# SCH_ESP32-Gate-Module_2024-04-19.net
KiCad netlist of a schematic drawn in EasyEDA
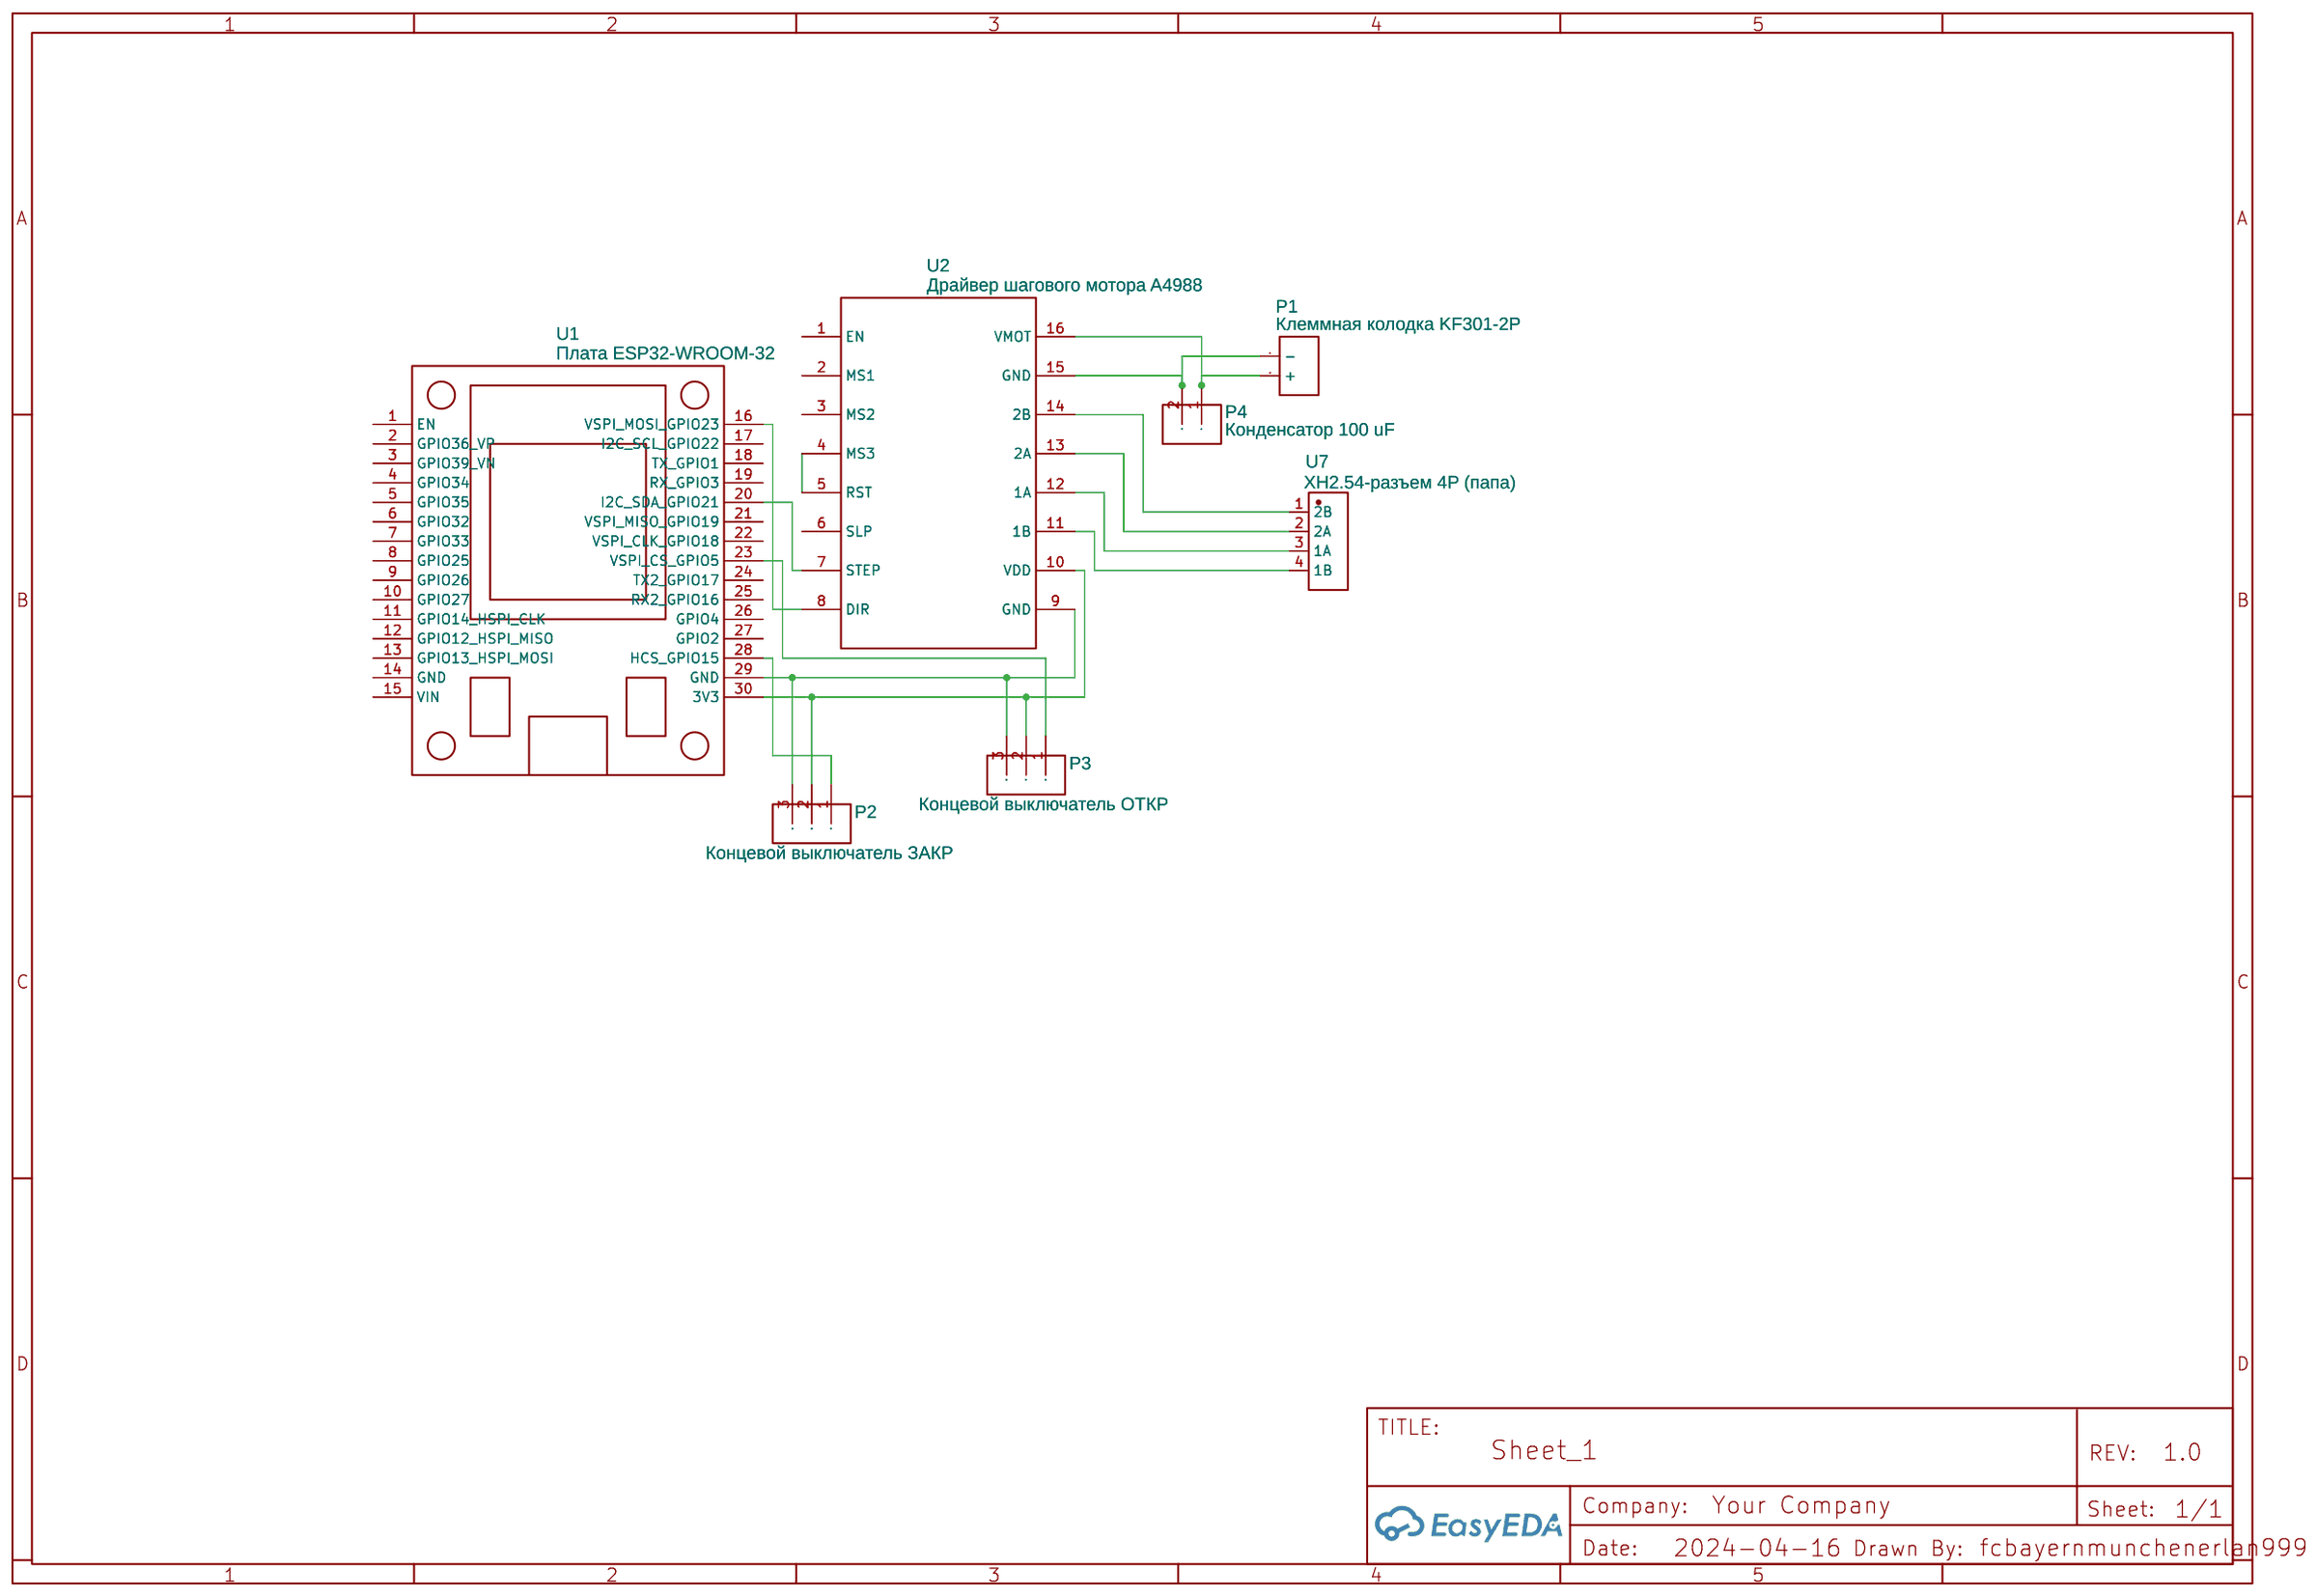
[diagram p0: schematic sheet]

(export (version "E")
  (design (tool "Eeschema 10.0.6"))
  (components
    (comp (ref "P1") (value "Клеммная колодка KF301-2P") (libsource (lib "") (part "CONN-TH_2P-P5.00")))
    (comp (ref "P2") (value "Концевой выключатель ЗАКР") (libsource (lib "") (part "3x2.54 XHP-3 JST case")))
    (comp (ref "P3") (value "Концевой выключатель ОТКР") (libsource (lib "") (part "3x2.54 XHP-3 JST case")))
    (comp (ref "P4") (value "Конденсатор 100 uF") (libsource (lib "") (part "2x2.54 XHP-2 JST case")))
    (comp (ref "U1") (value "Плата ESP32-WROOM-32") (libsource (lib "") (part "Плата ESP32 (вариант 2)")))
    (comp (ref "U2")
      (value "Драйвер шагового мотора A4988")
      (libsource (lib "") (part "A4988 Stepper Motor Driver Carrier"))
    )
    (comp (ref "U7")
      (value "XH2.54-разъем 4P (папа)")
      (fields
        (field (name "Manufacturer Part") "ZX-XH2.54-4PWZ")
        (field (name "Manufacturer") "Megastar(兆星)")
      )
      (libsource (lib "") (part "ZX-XH2.54-4PWZ"))
    )
  )
  (nets
    (net (code "1") (name "Net-(P1-+)") (class "Default")
      (node (ref "P1") (pin "2") (pinfunction "+_2") (pintype "unspecified"))
      (node (ref "P4") (pin "1") (pinfunction "1_1") (pintype "unspecified"))
      (node (ref "U2") (pin "16") (pinfunction "VMOT_16") (pintype "unspecified"))
    )
    (net (code "2") (name "Net-(P1--)") (class "Default")
      (node (ref "P1") (pin "1") (pinfunction "-_1") (pintype "unspecified"))
      (node (ref "P4") (pin "2") (pinfunction "2_2") (pintype "unspecified"))
      (node (ref "U2") (pin "15") (pinfunction "GND_15") (pintype "unspecified"))
    )
    (net (code "3") (name "Net-(P2-Pad3)") (class "Default")
      (node (ref "P2") (pin "3") (pinfunction "3_3") (pintype "unspecified"))
      (node (ref "P3") (pin "3") (pinfunction "3_3") (pintype "unspecified"))
      (node (ref "U1") (pin "29") (pinfunction "GND_29") (pintype "bidirectional"))
      (node (ref "U2") (pin "9") (pinfunction "GND_9") (pintype "unspecified"))
    )
    (net (code "4") (name "Net-(U1-3V3)") (class "Default")
      (node (ref "P2") (pin "2") (pinfunction "2_2") (pintype "unspecified"))
      (node (ref "P3") (pin "2") (pinfunction "2_2") (pintype "unspecified"))
      (node (ref "U1") (pin "30") (pinfunction "3V3_30") (pintype "bidirectional"))
      (node (ref "U2") (pin "10") (pinfunction "VDD_10") (pintype "unspecified"))
    )
    (net (code "5") (name "Net-(U1-HCS_GPIO15)") (class "Default")
      (node (ref "P2") (pin "1") (pinfunction "1_1") (pintype "unspecified"))
      (node (ref "U1") (pin "28") (pinfunction "HCS_GPIO15_28") (pintype "bidirectional"))
    )
    (net (code "6") (name "Net-(U1-I2C_SDA_GPIO21)") (class "Default")
      (node (ref "U1") (pin "20") (pinfunction "I2C_SDA_GPIO21_20") (pintype "bidirectional"))
      (node (ref "U2") (pin "7") (pinfunction "STEP_7") (pintype "unspecified"))
    )
    (net (code "7") (name "Net-(U1-VSPI_CS_GPIO5)") (class "Default")
      (node (ref "P3") (pin "1") (pinfunction "1_1") (pintype "unspecified"))
      (node (ref "U1") (pin "23") (pinfunction "VSPI_CS_GPIO5_23") (pintype "bidirectional"))
    )
    (net (code "8") (name "Net-(U1-VSPI_MOSI_GPIO23)") (class "Default")
      (node (ref "U1") (pin "16") (pinfunction "VSPI_MOSI_GPIO23_16") (pintype "passive"))
      (node (ref "U2") (pin "8") (pinfunction "DIR_8") (pintype "unspecified"))
    )
    (net (code "9") (name "Net-(U2-1A)") (class "Default")
      (node (ref "U2") (pin "12") (pinfunction "1A_12") (pintype "unspecified"))
      (node (ref "U7") (pin "3") (pinfunction "1A_3") (pintype "unspecified"))
    )
    (net (code "10") (name "Net-(U2-1B)") (class "Default")
      (node (ref "U2") (pin "11") (pinfunction "1B_11") (pintype "unspecified"))
      (node (ref "U7") (pin "4") (pinfunction "1B_4") (pintype "unspecified"))
    )
    (net (code "11") (name "Net-(U2-2A)") (class "Default")
      (node (ref "U2") (pin "13") (pinfunction "2A_13") (pintype "unspecified"))
      (node (ref "U7") (pin "2") (pinfunction "2A_2") (pintype "unspecified"))
    )
    (net (code "12") (name "Net-(U2-2B)") (class "Default")
      (node (ref "U2") (pin "14") (pinfunction "2B_14") (pintype "unspecified"))
      (node (ref "U7") (pin "1") (pinfunction "2B_1") (pintype "unspecified"))
    )
    (net (code "13") (name "Net-(U2-MS3)") (class "Default")
      (node (ref "U2") (pin "4") (pinfunction "MS3_4") (pintype "unspecified"))
      (node (ref "U2") (pin "5") (pinfunction "RST_5") (pintype "unspecified"))
    )
    (net (code "14") (name "unconnected-(U1-EN-Pad1)") (class "Default")
      (node (ref "U1") (pin "1") (pinfunction "EN_1") (pintype "passive"))
    )
    (net (code "15") (name "unconnected-(U1-GND-Pad14)") (class "Default")
      (node (ref "U1") (pin "14") (pinfunction "GND_14") (pintype "passive"))
    )
    (net (code "16") (name "unconnected-(U1-GPIO2-Pad27)") (class "Default")
      (node (ref "U1") (pin "27") (pinfunction "GPIO2_27") (pintype "bidirectional"))
    )
    (net (code "17") (name "unconnected-(U1-GPIO4-Pad26)") (class "Default")
      (node (ref "U1") (pin "26") (pinfunction "GPIO4_26") (pintype "bidirectional"))
    )
    (net (code "18") (name "unconnected-(U1-GPIO12_HSPI_MISO-Pad12)") (class "Default")
      (node (ref "U1") (pin "12") (pinfunction "GPIO12_HSPI_MISO_12") (pintype "bidirectional"))
    )
    (net (code "19") (name "unconnected-(U1-GPIO13_HSPI_MOSI-Pad13)") (class "Default")
      (node (ref "U1") (pin "13") (pinfunction "GPIO13_HSPI_MOSI_13") (pintype "bidirectional"))
    )
    (net (code "20") (name "unconnected-(U1-GPIO14_HSPI_CLK-Pad11)") (class "Default")
      (node (ref "U1") (pin "11") (pinfunction "GPIO14_HSPI_CLK_11") (pintype "bidirectional"))
    )
    (net (code "21") (name "unconnected-(U1-GPIO25-Pad8)") (class "Default")
      (node (ref "U1") (pin "8") (pinfunction "GPIO25_8") (pintype "bidirectional"))
    )
    (net (code "22") (name "unconnected-(U1-GPIO26-Pad9)") (class "Default")
      (node (ref "U1") (pin "9") (pinfunction "GPIO26_9") (pintype "bidirectional"))
    )
    (net (code "23") (name "unconnected-(U1-GPIO27-Pad10)") (class "Default")
      (node (ref "U1") (pin "10") (pinfunction "GPIO27_10") (pintype "bidirectional"))
    )
    (net (code "24") (name "unconnected-(U1-GPIO32-Pad6)") (class "Default")
      (node (ref "U1") (pin "6") (pinfunction "GPIO32_6") (pintype "bidirectional"))
    )
    (net (code "25") (name "unconnected-(U1-GPIO33-Pad7)") (class "Default")
      (node (ref "U1") (pin "7") (pinfunction "GPIO33_7") (pintype "bidirectional"))
    )
    (net (code "26") (name "unconnected-(U1-GPIO34-Pad4)") (class "Default")
      (node (ref "U1") (pin "4") (pinfunction "GPIO34_4") (pintype "bidirectional"))
    )
    (net (code "27") (name "unconnected-(U1-GPIO35-Pad5)") (class "Default")
      (node (ref "U1") (pin "5") (pinfunction "GPIO35_5") (pintype "bidirectional"))
    )
    (net (code "28") (name "unconnected-(U1-GPIO36_VP-Pad2)") (class "Default")
      (node (ref "U1") (pin "2") (pinfunction "GPIO36_VP_2") (pintype "bidirectional"))
    )
    (net (code "29") (name "unconnected-(U1-GPIO39_VN-Pad3)") (class "Default")
      (node (ref "U1") (pin "3") (pinfunction "GPIO39_VN_3") (pintype "bidirectional"))
    )
    (net (code "30") (name "unconnected-(U1-I2C_SCL_GPIO22-Pad17)") (class "Default")
      (node (ref "U1") (pin "17") (pinfunction "I2C_SCL_GPIO22_17") (pintype "bidirectional"))
    )
    (net (code "31") (name "unconnected-(U1-RX2_GPIO16-Pad25)") (class "Default")
      (node (ref "U1") (pin "25") (pinfunction "RX2_GPIO16_25") (pintype "bidirectional"))
    )
    (net (code "32") (name "unconnected-(U1-RX_GPIO3-Pad19)") (class "Default")
      (node (ref "U1") (pin "19") (pinfunction "RX_GPIO3_19") (pintype "bidirectional"))
    )
    (net (code "33") (name "unconnected-(U1-TX2_GPIO17-Pad24)") (class "Default")
      (node (ref "U1") (pin "24") (pinfunction "TX2_GPIO17_24") (pintype "bidirectional"))
    )
    (net (code "34") (name "unconnected-(U1-TX_GPIO1-Pad18)") (class "Default")
      (node (ref "U1") (pin "18") (pinfunction "TX_GPIO1_18") (pintype "bidirectional"))
    )
    (net (code "35") (name "unconnected-(U1-VIN-Pad15)") (class "Default")
      (node (ref "U1") (pin "15") (pinfunction "VIN_15") (pintype "bidirectional"))
    )
    (net (code "36") (name "unconnected-(U1-VSPI_CLK_GPIO18-Pad22)") (class "Default")
      (node (ref "U1") (pin "22") (pinfunction "VSPI_CLK_GPIO18_22") (pintype "passive"))
    )
    (net (code "37") (name "unconnected-(U1-VSPI_MISO_GPIO19-Pad21)") (class "Default")
      (node (ref "U1") (pin "21") (pinfunction "VSPI_MISO_GPIO19_21") (pintype "bidirectional"))
    )
    (net (code "38") (name "unconnected-(U2-EN-Pad1)") (class "Default")
      (node (ref "U2") (pin "1") (pinfunction "EN_1") (pintype "unspecified"))
    )
    (net (code "39") (name "unconnected-(U2-MS1-Pad2)") (class "Default")
      (node (ref "U2") (pin "2") (pinfunction "MS1_2") (pintype "unspecified"))
    )
    (net (code "40") (name "unconnected-(U2-MS2-Pad3)") (class "Default")
      (node (ref "U2") (pin "3") (pinfunction "MS2_3") (pintype "unspecified"))
    )
    (net (code "41") (name "unconnected-(U2-SLP-Pad6)") (class "Default")
      (node (ref "U2") (pin "6") (pinfunction "SLP_6") (pintype "unspecified"))
    )
  )
)
